# wavelet7.net
KiCad netlist of a schematic drawn in EAGLE
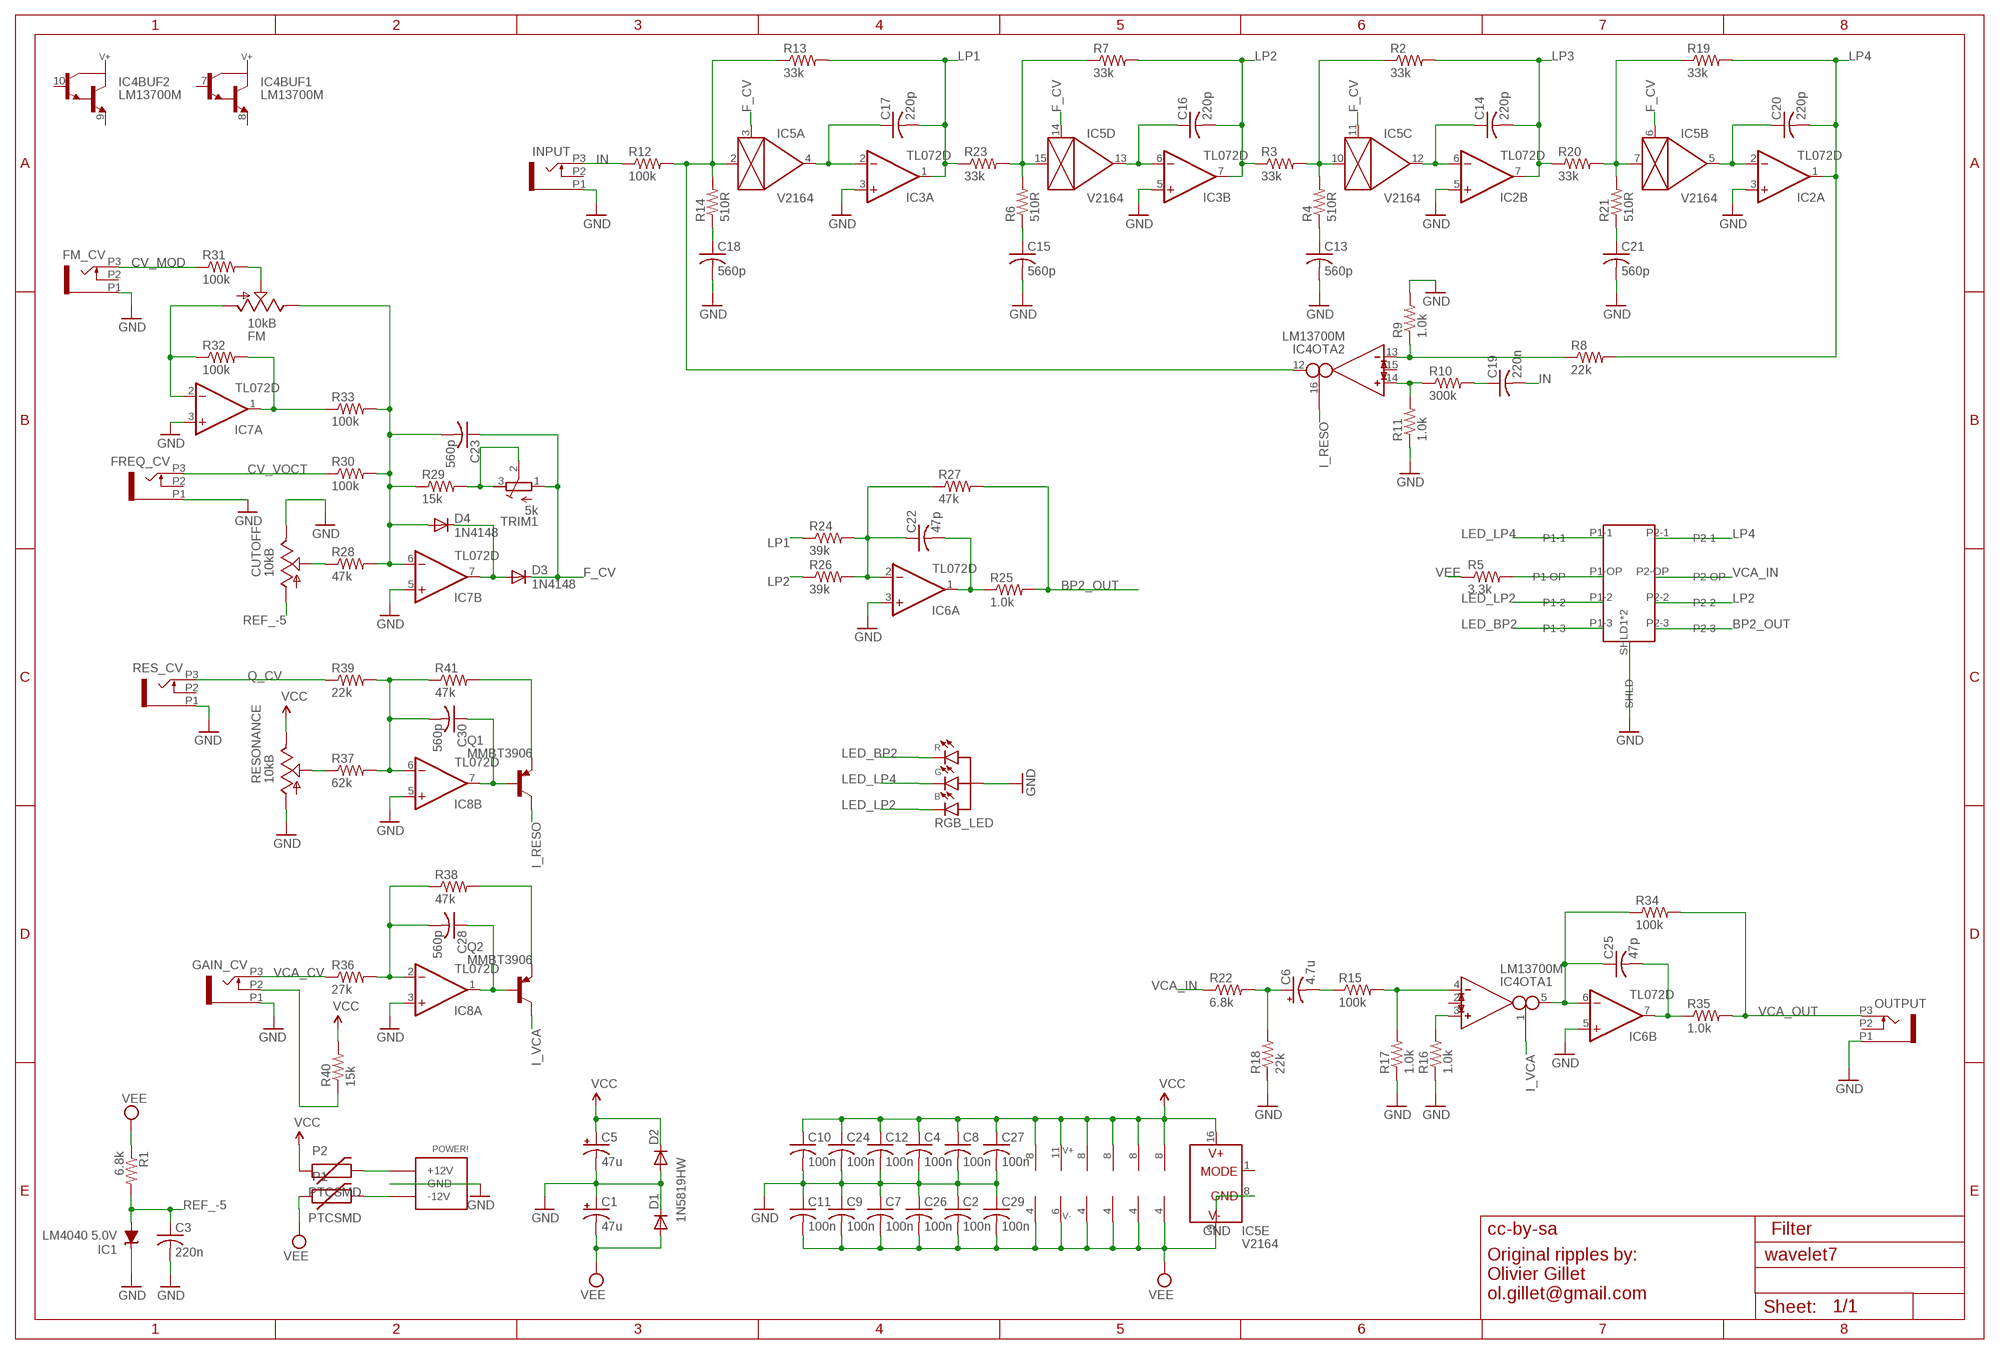
[diagram p0: schematic, sheet 1]

(export (version "E")
  (design (tool "Eeschema 10.0.6"))
  (components
    (comp (ref "C1")
      (value "47u")
      (footprint "eagle-import:PANASONIC_D")
      (libsource (lib "eagle-import") (part "CPOL-USD"))
    )
    (comp (ref "C2")
      (value "100n")
      (footprint "eagle-import:C0603")
      (libsource (lib "eagle-import") (part "C-USC0603"))
    )
    (comp (ref "C3")
      (value "220n")
      (footprint "eagle-import:C0603")
      (libsource (lib "eagle-import") (part "C-USC0603"))
    )
    (comp (ref "C4")
      (value "100n")
      (footprint "eagle-import:C0603")
      (libsource (lib "eagle-import") (part "C-USC0603"))
    )
    (comp (ref "C5")
      (value "47u")
      (footprint "eagle-import:PANASONIC_D")
      (libsource (lib "eagle-import") (part "CPOL-USD"))
    )
    (comp (ref "C6")
      (value "4.7u")
      (footprint "eagle-import:PANASONIC_B")
      (libsource (lib "eagle-import") (part "CPOL-USB"))
    )
    (comp (ref "C7")
      (value "100n")
      (footprint "eagle-import:C0603")
      (libsource (lib "eagle-import") (part "C-USC0603"))
    )
    (comp (ref "C8")
      (value "100n")
      (footprint "eagle-import:C0603")
      (libsource (lib "eagle-import") (part "C-USC0603"))
    )
    (comp (ref "C9")
      (value "100n")
      (footprint "eagle-import:C0603")
      (libsource (lib "eagle-import") (part "C-USC0603"))
    )
    (comp (ref "C10")
      (value "100n")
      (footprint "eagle-import:C0603")
      (libsource (lib "eagle-import") (part "C-USC0603"))
    )
    (comp (ref "C11")
      (value "100n")
      (footprint "eagle-import:C0603")
      (libsource (lib "eagle-import") (part "C-USC0603"))
    )
    (comp (ref "C12")
      (value "100n")
      (footprint "eagle-import:C0603")
      (libsource (lib "eagle-import") (part "C-USC0603"))
    )
    (comp (ref "C13")
      (value "560p")
      (footprint "eagle-import:C0603")
      (libsource (lib "eagle-import") (part "C-USC0603"))
    )
    (comp (ref "C14")
      (value "220p")
      (footprint "eagle-import:C0603")
      (libsource (lib "eagle-import") (part "C-USC0603"))
    )
    (comp (ref "C15")
      (value "560p")
      (footprint "eagle-import:C0603")
      (libsource (lib "eagle-import") (part "C-USC0603"))
    )
    (comp (ref "C16")
      (value "220p")
      (footprint "eagle-import:C0603")
      (libsource (lib "eagle-import") (part "C-USC0603"))
    )
    (comp (ref "C17")
      (value "220p")
      (footprint "eagle-import:C0603")
      (libsource (lib "eagle-import") (part "C-USC0603"))
    )
    (comp (ref "C18")
      (value "560p")
      (footprint "eagle-import:C0603")
      (libsource (lib "eagle-import") (part "C-USC0603"))
    )
    (comp (ref "C19")
      (value "220n")
      (footprint "eagle-import:C0603")
      (libsource (lib "eagle-import") (part "C-USC0603"))
    )
    (comp (ref "C20")
      (value "220p")
      (footprint "eagle-import:C0603")
      (libsource (lib "eagle-import") (part "C-USC0603"))
    )
    (comp (ref "C21")
      (value "560p")
      (footprint "eagle-import:C0603")
      (libsource (lib "eagle-import") (part "C-USC0603"))
    )
    (comp (ref "C22")
      (value "47p")
      (footprint "eagle-import:C0603")
      (libsource (lib "eagle-import") (part "C-USC0603"))
    )
    (comp (ref "C23")
      (value "560p")
      (footprint "eagle-import:C0603")
      (libsource (lib "eagle-import") (part "C-USC0603"))
    )
    (comp (ref "C24")
      (value "100n")
      (footprint "eagle-import:C0603")
      (libsource (lib "eagle-import") (part "C-USC0603"))
    )
    (comp (ref "C25")
      (value "47p")
      (footprint "eagle-import:C0603")
      (libsource (lib "eagle-import") (part "C-USC0603"))
    )
    (comp (ref "C26")
      (value "100n")
      (footprint "eagle-import:C0603")
      (libsource (lib "eagle-import") (part "C-USC0603"))
    )
    (comp (ref "C27")
      (value "100n")
      (footprint "eagle-import:C0603")
      (libsource (lib "eagle-import") (part "C-USC0603"))
    )
    (comp (ref "C28")
      (value "560p")
      (footprint "eagle-import:C0603")
      (libsource (lib "eagle-import") (part "C-USC0603"))
    )
    (comp (ref "C29")
      (value "100n")
      (footprint "eagle-import:C0603")
      (libsource (lib "eagle-import") (part "C-USC0603"))
    )
    (comp (ref "C30")
      (value "560p")
      (footprint "eagle-import:C0603")
      (libsource (lib "eagle-import") (part "C-USC0603"))
    )
    (comp (ref "CUTOFF")
      (value "10kB")
      (footprint "eagle-import:ALPS_POT_VERTICAL_PS")
      (libsource (lib "eagle-import") (part "POT_USVERTICAL_PS"))
    )
    (comp (ref "D1")
      (value "1N5819HW")
      (footprint "eagle-import:SOD123")
      (libsource (lib "eagle-import") (part "DIODE-SOD123"))
    )
    (comp (ref "D2")
      (value "1N5819HW")
      (footprint "eagle-import:SOD123")
      (libsource (lib "eagle-import") (part "DIODE-SOD123"))
    )
    (comp (ref "D3")
      (value "1N4148")
      (footprint "eagle-import:SOD323-W")
      (libsource (lib "eagle-import") (part "DIODE-SOD323-W"))
    )
    (comp (ref "D4")
      (value "1N4148")
      (footprint "eagle-import:SOD323-W")
      (libsource (lib "eagle-import") (part "DIODE-SOD323-W"))
    )
    (comp (ref "FILTER_MODE")
      (value "APEM-MHS233K")
      (footprint "eagle-import:APEM-MHS233K")
      (libsource (lib "eagle-import") (part "APEM-MHS233K"))
    )
    (comp (ref "FM")
      (value "10kB")
      (footprint "eagle-import:ALPS_POT_VERTICAL_PS")
      (libsource (lib "eagle-import") (part "POT_USVERTICAL_PS"))
    )
    (comp (ref "FM_CV")
      (value "OG-PJ301_PJ301_THONKICONN")
      (footprint "eagle-import:OG-PJ301_WQP_PJ_301M6_NO_HOLE")
      (libsource (lib "eagle-import") (part "OG-PJ301_PJ301_THONKICONN"))
    )
    (comp (ref "FREQ_CV")
      (value "OG-PJ301_PJ301_THONKICONN")
      (footprint "eagle-import:OG-PJ301_WQP_PJ_301M6_NO_HOLE")
      (libsource (lib "eagle-import") (part "OG-PJ301_PJ301_THONKICONN"))
    )
    (comp (ref "GAIN_CV")
      (value "OG-PJ301_PJ301_THONKICONN")
      (footprint "eagle-import:OG-PJ301_WQP_PJ_301M6_NO_HOLE")
      (libsource (lib "eagle-import") (part "OG-PJ301_PJ301_THONKICONN"))
    )
    (comp (ref "IC1")
      (value "LM4040 5.0V")
      (footprint "eagle-import:DBZ_R-PDSO-G3")
      (libsource (lib "eagle-import") (part "LM4041DBZC12"))
    )
    (comp (ref "IC2")
      (value "TL072D")
      (footprint "eagle-import:SO08")
      (libsource (lib "eagle-import") (part "og-linear_TL072D"))
    )
    (comp (ref "IC3")
      (value "TL072D")
      (footprint "eagle-import:SO08")
      (libsource (lib "eagle-import") (part "og-linear_TL072D"))
    )
    (comp (ref "IC4")
      (value "LM13700M")
      (footprint "eagle-import:SO16")
      (libsource (lib "eagle-import") (part "LM13700M"))
    )
    (comp (ref "IC5")
      (value "V2164")
      (footprint "eagle-import:SOIC16N")
      (libsource (lib "eagle-import") (part "SSM2164S"))
    )
    (comp (ref "IC6")
      (value "TL072D")
      (footprint "eagle-import:SO08")
      (libsource (lib "eagle-import") (part "TL072D"))
    )
    (comp (ref "IC7")
      (value "TL072D")
      (footprint "eagle-import:SO08")
      (libsource (lib "eagle-import") (part "TL072D"))
    )
    (comp (ref "IC8")
      (value "TL072D")
      (footprint "eagle-import:SO08")
      (libsource (lib "eagle-import") (part "TL072D"))
    )
    (comp (ref "INPUT")
      (value "OG-PJ301_PJ301_THONKICONN")
      (footprint "eagle-import:OG-PJ301_WQP_PJ_301M6_NO_HOLE")
      (libsource (lib "eagle-import") (part "OG-PJ301_PJ301_THONKICONN"))
    )
    (comp (ref "OUTPUT")
      (value "OG-PJ301_PJ301_THONKICONN")
      (footprint "eagle-import:OG-PJ301_WQP_PJ_301M6_NO_HOLE")
      (libsource (lib "eagle-import") (part "OG-PJ301_PJ301_THONKICONN"))
    )
    (comp (ref "P1")
      (value "PTCSMD")
      (footprint "eagle-import:PTC-1206")
      (libsource (lib "eagle-import") (part "PTCSMD"))
    )
    (comp (ref "P2")
      (value "PTCSMD")
      (footprint "eagle-import:PTC-1206")
      (libsource (lib "eagle-import") (part "PTCSMD"))
    )
    (comp (ref "POWER!")
      (value "POWER_SIMPLE")
      (footprint "eagle-import:2X05_SMT_HEADER")
      (libsource (lib "eagle-import") (part "POWER_SIMPLE"))
    )
    (comp (ref "Q1")
      (value "MMBT3906")
      (footprint "eagle-import:SOT23-BEC")
      (libsource (lib "eagle-import") (part "-PNP-SOT23-BECMMBT3906LT1"))
    )
    (comp (ref "Q2")
      (value "MMBT3906")
      (footprint "eagle-import:SOT23-BEC")
      (libsource (lib "eagle-import") (part "-PNP-SOT23-BECMMBT3906LT1"))
    )
    (comp (ref "R1")
      (value "6.8k")
      (footprint "eagle-import:R0603")
      (libsource (lib "eagle-import") (part "resistor_R-US_R0603"))
    )
    (comp (ref "R2")
      (value "33k")
      (footprint "eagle-import:R0603")
      (libsource (lib "eagle-import") (part "R-US_R0603"))
    )
    (comp (ref "R3")
      (value "33k")
      (footprint "eagle-import:R0603")
      (libsource (lib "eagle-import") (part "R-US_R0603"))
    )
    (comp (ref "R4")
      (value "510R")
      (footprint "eagle-import:R0603")
      (libsource (lib "eagle-import") (part "R-US_R0603"))
    )
    (comp (ref "R5")
      (value "3.3k")
      (footprint "eagle-import:R0603")
      (libsource (lib "eagle-import") (part "R-US_R0603"))
    )
    (comp (ref "R6")
      (value "510R")
      (footprint "eagle-import:R0603")
      (libsource (lib "eagle-import") (part "R-US_R0603"))
    )
    (comp (ref "R7")
      (value "33k")
      (footprint "eagle-import:R0603")
      (libsource (lib "eagle-import") (part "R-US_R0603"))
    )
    (comp (ref "R8")
      (value "22k")
      (footprint "eagle-import:R0603")
      (libsource (lib "eagle-import") (part "R-US_R0603"))
    )
    (comp (ref "R9")
      (value "1.0k")
      (footprint "eagle-import:R0603")
      (libsource (lib "eagle-import") (part "R-US_R0603"))
    )
    (comp (ref "R10")
      (value "300k")
      (footprint "eagle-import:R0603")
      (libsource (lib "eagle-import") (part "R-US_R0603"))
    )
    (comp (ref "R11")
      (value "1.0k")
      (footprint "eagle-import:R0603")
      (libsource (lib "eagle-import") (part "R-US_R0603"))
    )
    (comp (ref "R12")
      (value "100k")
      (footprint "eagle-import:R0603")
      (libsource (lib "eagle-import") (part "R-US_R0603"))
    )
    (comp (ref "R13")
      (value "33k")
      (footprint "eagle-import:R0603")
      (libsource (lib "eagle-import") (part "R-US_R0603"))
    )
    (comp (ref "R14")
      (value "510R")
      (footprint "eagle-import:R0603")
      (libsource (lib "eagle-import") (part "R-US_R0603"))
    )
    (comp (ref "R15")
      (value "100k")
      (footprint "eagle-import:R0603")
      (libsource (lib "eagle-import") (part "R-US_R0603"))
    )
    (comp (ref "R16")
      (value "1.0k")
      (footprint "eagle-import:R0603")
      (libsource (lib "eagle-import") (part "R-US_R0603"))
    )
    (comp (ref "R17")
      (value "1.0k")
      (footprint "eagle-import:R0603")
      (libsource (lib "eagle-import") (part "R-US_R0603"))
    )
    (comp (ref "R18")
      (value "22k")
      (footprint "eagle-import:R0603")
      (libsource (lib "eagle-import") (part "R-US_R0603"))
    )
    (comp (ref "R19")
      (value "33k")
      (footprint "eagle-import:R0603")
      (libsource (lib "eagle-import") (part "R-US_R0603"))
    )
    (comp (ref "R20")
      (value "33k")
      (footprint "eagle-import:R0603")
      (libsource (lib "eagle-import") (part "R-US_R0603"))
    )
    (comp (ref "R21")
      (value "510R")
      (footprint "eagle-import:R0603")
      (libsource (lib "eagle-import") (part "R-US_R0603"))
    )
    (comp (ref "R22")
      (value "6.8k")
      (footprint "eagle-import:R0603")
      (libsource (lib "eagle-import") (part "R-US_R0603"))
    )
    (comp (ref "R23")
      (value "33k")
      (footprint "eagle-import:R0603")
      (libsource (lib "eagle-import") (part "R-US_R0603"))
    )
    (comp (ref "R24")
      (value "39k")
      (footprint "eagle-import:R0603")
      (libsource (lib "eagle-import") (part "R-US_R0603"))
    )
    (comp (ref "R25")
      (value "1.0k")
      (footprint "eagle-import:R0603")
      (libsource (lib "eagle-import") (part "R-US_R0603"))
    )
    (comp (ref "R26")
      (value "39k")
      (footprint "eagle-import:R0603")
      (libsource (lib "eagle-import") (part "R-US_R0603"))
    )
    (comp (ref "R27")
      (value "47k")
      (footprint "eagle-import:R0603")
      (libsource (lib "eagle-import") (part "R-US_R0603"))
    )
    (comp (ref "R28")
      (value "47k")
      (footprint "eagle-import:R0603")
      (libsource (lib "eagle-import") (part "R-US_R0603"))
    )
    (comp (ref "R29")
      (value "15k")
      (footprint "eagle-import:R0603")
      (libsource (lib "eagle-import") (part "R-US_R0603"))
    )
    (comp (ref "R30")
      (value "100k")
      (footprint "eagle-import:R0603")
      (libsource (lib "eagle-import") (part "R-US_R0603"))
    )
    (comp (ref "R31")
      (value "100k")
      (footprint "eagle-import:R0603")
      (libsource (lib "eagle-import") (part "R-US_R0603"))
    )
    (comp (ref "R32")
      (value "100k")
      (footprint "eagle-import:R0603")
      (libsource (lib "eagle-import") (part "R-US_R0603"))
    )
    (comp (ref "R33")
      (value "100k")
      (footprint "eagle-import:R0603")
      (libsource (lib "eagle-import") (part "R-US_R0603"))
    )
    (comp (ref "R34")
      (value "100k")
      (footprint "eagle-import:R0603")
      (libsource (lib "eagle-import") (part "R-US_R0603"))
    )
    (comp (ref "R35")
      (value "1.0k")
      (footprint "eagle-import:R0603")
      (libsource (lib "eagle-import") (part "R-US_R0603"))
    )
    (comp (ref "R36")
      (value "27k")
      (footprint "eagle-import:R0603")
      (libsource (lib "eagle-import") (part "R-US_R0603"))
    )
    (comp (ref "R37")
      (value "62k")
      (footprint "eagle-import:R0603")
      (libsource (lib "eagle-import") (part "R-US_R0603"))
    )
    (comp (ref "R38")
      (value "47k")
      (footprint "eagle-import:R0603")
      (libsource (lib "eagle-import") (part "R-US_R0603"))
    )
    (comp (ref "R39")
      (value "22k")
      (footprint "eagle-import:R0603")
      (libsource (lib "eagle-import") (part "R-US_R0603"))
    )
    (comp (ref "R40")
      (value "15k")
      (footprint "eagle-import:R0603")
      (libsource (lib "eagle-import") (part "R-US_R0603"))
    )
    (comp (ref "R41")
      (value "47k")
      (footprint "eagle-import:R0603")
      (libsource (lib "eagle-import") (part "R-US_R0603"))
    )
    (comp (ref "RESONANCE")
      (value "10kB")
      (footprint "eagle-import:ALPS_POT_VERTICAL_PS")
      (libsource (lib "eagle-import") (part "POT_USVERTICAL_PS"))
    )
    (comp (ref "RES_CV")
      (value "OG-PJ301_PJ301_THONKICONN")
      (footprint "eagle-import:OG-PJ301_WQP_PJ_301M6_NO_HOLE")
      (libsource (lib "eagle-import") (part "OG-PJ301_PJ301_THONKICONN"))
    )
    (comp (ref "RGB_LED")
      (value "LED-RGB-CA-HEBEI")
      (footprint "eagle-import:PLCC4")
      (libsource (lib "eagle-import") (part "LED-RGB-CA-HEBEI"))
    )
    (comp (ref "TRIM1")
      (value "5k")
      (footprint "eagle-import:RTRIM3296X")
      (libsource (lib "eagle-import") (part "R-TRIMM3296X"))
    )
  )
  (nets
    (net (code "1") (name "/BP2_OUT") (class "Default")
      (node (ref "FILTER_MODE") (pin "P2-3") (pinfunction "P2-3_P2-3") (pintype "bidirectional"))
      (node (ref "R25") (pin "2") (pinfunction "2_2") (pintype "passive"))
      (node (ref "R27") (pin "2") (pinfunction "2_2") (pintype "passive"))
    )
    (net (code "2") (name "/CV_MOD") (class "Default")
      (node (ref "FM_CV") (pin "P3") (pinfunction "3_P3") (pintype "passive"))
      (node (ref "R31") (pin "1") (pinfunction "1_1") (pintype "passive"))
    )
    (net (code "3") (name "/CV_VOCT") (class "Default")
      (node (ref "FREQ_CV") (pin "P3") (pinfunction "3_P3") (pintype "passive"))
      (node (ref "R30") (pin "1") (pinfunction "1_1") (pintype "passive"))
    )
    (net (code "4") (name "/F_CV") (class "Default")
      (node (ref "C23") (pin "1") (pinfunction "1_1") (pintype "passive"))
      (node (ref "D3") (pin "C") (pinfunction "C_C") (pintype "passive"))
      (node (ref "IC5") (pin "11") (pinfunction "CTRL_11") (pintype "input"))
      (node (ref "IC5") (pin "14") (pinfunction "CTRL_14") (pintype "input"))
      (node (ref "IC5") (pin "3") (pinfunction "CTRL_3") (pintype "input"))
      (node (ref "IC5") (pin "6") (pinfunction "CTRL_6") (pintype "input"))
      (node (ref "TRIM1") (pin "1") (pinfunction "E_1") (pintype "passive"))
    )
    (net (code "5") (name "/IN") (class "Default")
      (node (ref "C19") (pin "2") (pinfunction "2_2") (pintype "passive"))
      (node (ref "INPUT") (pin "P3") (pinfunction "3_P3") (pintype "passive"))
      (node (ref "R12") (pin "1") (pinfunction "1_1") (pintype "passive"))
    )
    (net (code "6") (name "/I_RESO") (class "Default")
      (node (ref "IC4") (pin "16") (pinfunction "I_BIAS_16") (pintype "input"))
      (node (ref "Q1") (pin "C") (pinfunction "C_C") (pintype "passive"))
    )
    (net (code "7") (name "/I_VCA") (class "Default")
      (node (ref "IC4") (pin "1") (pinfunction "I_BIAS_1") (pintype "input"))
      (node (ref "Q2") (pin "C") (pinfunction "C_C") (pintype "passive"))
    )
    (net (code "8") (name "/LED_BP2") (class "Default")
      (node (ref "FILTER_MODE") (pin "P1-3") (pinfunction "P1-3_P1-3") (pintype "bidirectional"))
      (node (ref "RGB_LED") (pin "P$1") (pinfunction "CR_P$1") (pintype "passive"))
    )
    (net (code "9") (name "/LED_LP2") (class "Default")
      (node (ref "FILTER_MODE") (pin "P1-2") (pinfunction "P1-2_P1-2") (pintype "bidirectional"))
      (node (ref "RGB_LED") (pin "P$3") (pinfunction "CB_P$3") (pintype "passive"))
    )
    (net (code "10") (name "/LED_LP4") (class "Default")
      (node (ref "FILTER_MODE") (pin "P1-1") (pinfunction "P1-1_P1-1") (pintype "bidirectional"))
      (node (ref "RGB_LED") (pin "P$4") (pinfunction "CG_P$4") (pintype "passive"))
    )
    (net (code "11") (name "/LP1") (class "Default")
      (node (ref "C17") (pin "2") (pinfunction "2_2") (pintype "passive"))
      (node (ref "IC3") (pin "1") (pinfunction "OUT_1") (pintype "output"))
      (node (ref "R13") (pin "2") (pinfunction "2_2") (pintype "passive"))
      (node (ref "R23") (pin "1") (pinfunction "1_1") (pintype "passive"))
      (node (ref "R24") (pin "1") (pinfunction "1_1") (pintype "passive"))
    )
    (net (code "12") (name "/LP2") (class "Default")
      (node (ref "C16") (pin "2") (pinfunction "2_2") (pintype "passive"))
      (node (ref "FILTER_MODE") (pin "P2-2") (pinfunction "P2-2_P2-2") (pintype "bidirectional"))
      (node (ref "IC3") (pin "7") (pinfunction "OUT_7") (pintype "output"))
      (node (ref "R26") (pin "1") (pinfunction "1_1") (pintype "passive"))
      (node (ref "R3") (pin "1") (pinfunction "1_1") (pintype "passive"))
      (node (ref "R7") (pin "2") (pinfunction "2_2") (pintype "passive"))
    )
    (net (code "13") (name "/LP3") (class "Default")
      (node (ref "C14") (pin "2") (pinfunction "2_2") (pintype "passive"))
      (node (ref "IC2") (pin "7") (pinfunction "OUT_7") (pintype "output"))
      (node (ref "R2") (pin "2") (pinfunction "2_2") (pintype "passive"))
      (node (ref "R20") (pin "1") (pinfunction "1_1") (pintype "passive"))
    )
    (net (code "14") (name "/LP4") (class "Default")
      (node (ref "C20") (pin "2") (pinfunction "2_2") (pintype "passive"))
      (node (ref "FILTER_MODE") (pin "P2-1") (pinfunction "P2-1_P2-1") (pintype "bidirectional"))
      (node (ref "IC2") (pin "1") (pinfunction "OUT_1") (pintype "output"))
      (node (ref "R19") (pin "2") (pinfunction "2_2") (pintype "passive"))
      (node (ref "R8") (pin "2") (pinfunction "2_2") (pintype "passive"))
    )
    (net (code "15") (name "/Q_CV") (class "Default")
      (node (ref "R39") (pin "1") (pinfunction "1_1") (pintype "passive"))
      (node (ref "RES_CV") (pin "P3") (pinfunction "3_P3") (pintype "passive"))
    )
    (net (code "16") (name "/REF_-5") (class "Default")
      (node (ref "C3") (pin "1") (pinfunction "1_1") (pintype "passive"))
      (node (ref "CUTOFF") (pin "P$3") (pinfunction "A_P$3") (pintype "passive"))
      (node (ref "IC1") (pin "2") (pinfunction "A_2") (pintype "passive"))
      (node (ref "R1") (pin "2") (pinfunction "2_2") (pintype "passive"))
    )
    (net (code "17") (name "/VCA_CV") (class "Default")
      (node (ref "GAIN_CV") (pin "P3") (pinfunction "3_P3") (pintype "passive"))
      (node (ref "R36") (pin "1") (pinfunction "1_1") (pintype "passive"))
    )
    (net (code "18") (name "/VCA_IN") (class "Default")
      (node (ref "FILTER_MODE") (pin "P2-OP") (pinfunction "P2-OP_P2-OP") (pintype "bidirectional"))
      (node (ref "R22") (pin "1") (pinfunction "1_1") (pintype "passive"))
    )
    (net (code "19") (name "/VCA_OUT") (class "Default")
      (node (ref "OUTPUT") (pin "P3") (pinfunction "3_P3") (pintype "passive"))
      (node (ref "R34") (pin "2") (pinfunction "2_2") (pintype "passive"))
      (node (ref "R35") (pin "2") (pinfunction "2_2") (pintype "passive"))
    )
    (net (code "20") (name "GND") (class "Default")
      (node (ref "C1") (pin "+") (pinfunction "+_+") (pintype "passive"))
      (node (ref "C10") (pin "2") (pinfunction "2_2") (pintype "passive"))
      (node (ref "C11") (pin "1") (pinfunction "1_1") (pintype "passive"))
      (node (ref "C12") (pin "2") (pinfunction "2_2") (pintype "passive"))
      (node (ref "C13") (pin "2") (pinfunction "2_2") (pintype "passive"))
      (node (ref "C15") (pin "2") (pinfunction "2_2") (pintype "passive"))
      (node (ref "C18") (pin "2") (pinfunction "2_2") (pintype "passive"))
      (node (ref "C2") (pin "1") (pinfunction "1_1") (pintype "passive"))
      (node (ref "C21") (pin "2") (pinfunction "2_2") (pintype "passive"))
      (node (ref "C24") (pin "2") (pinfunction "2_2") (pintype "passive"))
      (node (ref "C26") (pin "1") (pinfunction "1_1") (pintype "passive"))
      (node (ref "C27") (pin "2") (pinfunction "2_2") (pintype "passive"))
      (node (ref "C29") (pin "1") (pinfunction "1_1") (pintype "passive"))
      (node (ref "C3") (pin "2") (pinfunction "2_2") (pintype "passive"))
      (node (ref "C4") (pin "2") (pinfunction "2_2") (pintype "passive"))
      (node (ref "C5") (pin "-") (pinfunction "-_-") (pintype "passive"))
      (node (ref "C7") (pin "1") (pinfunction "1_1") (pintype "passive"))
      (node (ref "C8") (pin "2") (pinfunction "2_2") (pintype "passive"))
      (node (ref "C9") (pin "1") (pinfunction "1_1") (pintype "passive"))
      (node (ref "CUTOFF") (pin "P$1") (pinfunction "E_P$1") (pintype "passive"))
      (node (ref "D1") (pin "C") (pinfunction "C_C") (pintype "passive"))
      (node (ref "D2") (pin "A") (pinfunction "A_A") (pintype "passive"))
      (node (ref "FILTER_MODE") (pin "SHLD1") (pinfunction "SHLD_SHLD1") (pintype "bidirectional"))
      (node (ref "FILTER_MODE") (pin "SHLD2") (pinfunction "SHLD_SHLD2") (pintype "bidirectional"))
      (node (ref "FM_CV") (pin "P1") (pinfunction "1_P1") (pintype "passive"))
      (node (ref "FREQ_CV") (pin "P1") (pinfunction "1_P1") (pintype "passive"))
      (node (ref "GAIN_CV") (pin "P1") (pinfunction "1_P1") (pintype "passive"))
      (node (ref "IC1") (pin "1") (pinfunction "C_1") (pintype "passive"))
      (node (ref "IC2") (pin "3") (pinfunction "+IN_3") (pintype "input"))
      (node (ref "IC2") (pin "5") (pinfunction "+IN_5") (pintype "input"))
      (node (ref "IC3") (pin "3") (pinfunction "+IN_3") (pintype "input"))
      (node (ref "IC3") (pin "5") (pinfunction "+IN_5") (pintype "input"))
      (node (ref "IC5") (pin "8") (pinfunction "GND_8") (pintype "power_in"))
      (node (ref "IC6") (pin "3") (pinfunction "+IN_3") (pintype "input"))
      (node (ref "IC6") (pin "5") (pinfunction "+IN_5") (pintype "input"))
      (node (ref "IC7") (pin "3") (pinfunction "+IN_3") (pintype "input"))
      (node (ref "IC7") (pin "5") (pinfunction "+IN_5") (pintype "input"))
      (node (ref "IC8") (pin "3") (pinfunction "+IN_3") (pintype "input"))
      (node (ref "IC8") (pin "5") (pinfunction "+IN_5") (pintype "input"))
      (node (ref "INPUT") (pin "P1") (pinfunction "1_P1") (pintype "passive"))
      (node (ref "OUTPUT") (pin "P1") (pinfunction "1_P1") (pintype "passive"))
      (node (ref "POWER!") (pin "3") (pinfunction "GND_3") (pintype "bidirectional"))
      (node (ref "POWER!") (pin "4") (pinfunction "GND_4") (pintype "bidirectional"))
      (node (ref "POWER!") (pin "5") (pinfunction "GND_5") (pintype "bidirectional"))
      (node (ref "POWER!") (pin "6") (pinfunction "GND_6") (pintype "bidirectional"))
      (node (ref "POWER!") (pin "7") (pinfunction "GND_7") (pintype "bidirectional"))
      (node (ref "POWER!") (pin "8") (pinfunction "GND_8") (pintype "bidirectional"))
      (node (ref "R11") (pin "1") (pinfunction "1_1") (pintype "passive"))
      (node (ref "R16") (pin "1") (pinfunction "1_1") (pintype "passive"))
      (node (ref "R17") (pin "1") (pinfunction "1_1") (pintype "passive"))
      (node (ref "R18") (pin "1") (pinfunction "1_1") (pintype "passive"))
      (node (ref "R9") (pin "2") (pinfunction "2_2") (pintype "passive"))
      (node (ref "RESONANCE") (pin "P$3") (pinfunction "A_P$3") (pintype "passive"))
      (node (ref "RES_CV") (pin "P1") (pinfunction "1_P1") (pintype "passive"))
      (node (ref "RGB_LED") (pin "P$2") (pinfunction "A_P$2") (pintype "passive"))
    )
    (net (code "21") (name "Net-(C6-Pad+)") (class "Default")
      (node (ref "C6") (pin "+") (pinfunction "+_+") (pintype "passive"))
      (node (ref "R18") (pin "2") (pinfunction "2_2") (pintype "passive"))
      (node (ref "R22") (pin "2") (pinfunction "2_2") (pintype "passive"))
    )
    (net (code "22") (name "Net-(C6-Pad-)") (class "Default")
      (node (ref "C6") (pin "-") (pinfunction "-_-") (pintype "passive"))
      (node (ref "R15") (pin "1") (pinfunction "1_1") (pintype "passive"))
    )
    (net (code "23") (name "Net-(C13-Pad1)") (class "Default")
      (node (ref "C13") (pin "1") (pinfunction "1_1") (pintype "passive"))
      (node (ref "R4") (pin "1") (pinfunction "1_1") (pintype "passive"))
    )
    (net (code "24") (name "Net-(C15-Pad1)") (class "Default")
      (node (ref "C15") (pin "1") (pinfunction "1_1") (pintype "passive"))
      (node (ref "R6") (pin "1") (pinfunction "1_1") (pintype "passive"))
    )
    (net (code "25") (name "Net-(C18-Pad1)") (class "Default")
      (node (ref "C18") (pin "1") (pinfunction "1_1") (pintype "passive"))
      (node (ref "R14") (pin "1") (pinfunction "1_1") (pintype "passive"))
    )
    (net (code "26") (name "Net-(C19-Pad1)") (class "Default")
      (node (ref "C19") (pin "1") (pinfunction "1_1") (pintype "passive"))
      (node (ref "R10") (pin "2") (pinfunction "2_2") (pintype "passive"))
    )
    (net (code "27") (name "Net-(C21-Pad1)") (class "Default")
      (node (ref "C21") (pin "1") (pinfunction "1_1") (pintype "passive"))
      (node (ref "R21") (pin "1") (pinfunction "1_1") (pintype "passive"))
    )
    (net (code "28") (name "Net-(CUTOFF-S)") (class "Default")
      (node (ref "CUTOFF") (pin "P$2") (pinfunction "S_P$2") (pintype "passive"))
      (node (ref "R28") (pin "1") (pinfunction "1_1") (pintype "passive"))
    )
    (net (code "29") (name "Net-(FILTER_MODE-PadP1-OP)") (class "Default")
      (node (ref "FILTER_MODE") (pin "P1-OP") (pinfunction "P1-OP_P1-OP") (pintype "bidirectional"))
      (node (ref "R5") (pin "2") (pinfunction "2_2") (pintype "passive"))
    )
    (net (code "30") (name "Net-(FM-A)") (class "Default")
      (node (ref "FM") (pin "P$3") (pinfunction "A_P$3") (pintype "passive"))
      (node (ref "IC7") (pin "2") (pinfunction "-IN_2") (pintype "input"))
      (node (ref "R32") (pin "1") (pinfunction "1_1") (pintype "passive"))
    )
    (net (code "31") (name "Net-(FM-E)") (class "Default")
      (node (ref "C23") (pin "2") (pinfunction "2_2") (pintype "passive"))
      (node (ref "D4") (pin "A") (pinfunction "A_A") (pintype "passive"))
      (node (ref "FM") (pin "P$1") (pinfunction "E_P$1") (pintype "passive"))
      (node (ref "IC7") (pin "6") (pinfunction "-IN_6") (pintype "input"))
      (node (ref "R28") (pin "2") (pinfunction "2_2") (pintype "passive"))
      (node (ref "R29") (pin "1") (pinfunction "1_1") (pintype "passive"))
      (node (ref "R30") (pin "2") (pinfunction "2_2") (pintype "passive"))
      (node (ref "R33") (pin "2") (pinfunction "2_2") (pintype "passive"))
    )
    (net (code "32") (name "Net-(FM-S)") (class "Default")
      (node (ref "FM") (pin "P$2") (pinfunction "S_P$2") (pintype "passive"))
      (node (ref "R31") (pin "2") (pinfunction "2_2") (pintype "passive"))
    )
    (net (code "33") (name "Net-(GAIN_CV-2)") (class "Default")
      (node (ref "GAIN_CV") (pin "P2") (pinfunction "2_P2") (pintype "passive"))
      (node (ref "R40") (pin "1") (pinfunction "1_1") (pintype "passive"))
    )
    (net (code "34") (name "Net-(IC2A--IN)") (class "Default")
      (node (ref "C20") (pin "1") (pinfunction "1_1") (pintype "passive"))
      (node (ref "IC2") (pin "2") (pinfunction "-IN_2") (pintype "input"))
      (node (ref "IC5") (pin "5") (pinfunction "OUT_5") (pintype "output"))
    )
    (net (code "35") (name "Net-(IC2B--IN)") (class "Default")
      (node (ref "C14") (pin "1") (pinfunction "1_1") (pintype "passive"))
      (node (ref "IC2") (pin "6") (pinfunction "-IN_6") (pintype "input"))
      (node (ref "IC5") (pin "12") (pinfunction "OUT_12") (pintype "output"))
    )
    (net (code "36") (name "Net-(IC3A--IN)") (class "Default")
      (node (ref "C17") (pin "1") (pinfunction "1_1") (pintype "passive"))
      (node (ref "IC3") (pin "2") (pinfunction "-IN_2") (pintype "input"))
      (node (ref "IC5") (pin "4") (pinfunction "OUT_4") (pintype "output"))
    )
    (net (code "37") (name "Net-(IC3B--IN)") (class "Default")
      (node (ref "C16") (pin "1") (pinfunction "1_1") (pintype "passive"))
      (node (ref "IC3") (pin "6") (pinfunction "-IN_6") (pintype "input"))
      (node (ref "IC5") (pin "13") (pinfunction "OUT_13") (pintype "output"))
    )
    (net (code "38") (name "Net-(IC4C-IN_N)") (class "Default")
      (node (ref "IC4") (pin "4") (pinfunction "IN_N_4") (pintype "input"))
      (node (ref "R15") (pin "2") (pinfunction "2_2") (pintype "passive"))
      (node (ref "R17") (pin "2") (pinfunction "2_2") (pintype "passive"))
    )
    (net (code "39") (name "Net-(IC4C-IN_P)") (class "Default")
      (node (ref "IC4") (pin "3") (pinfunction "IN_P_3") (pintype "input"))
      (node (ref "R16") (pin "2") (pinfunction "2_2") (pintype "passive"))
    )
    (net (code "40") (name "Net-(IC4C-OUT)") (class "Default")
      (node (ref "C25") (pin "1") (pinfunction "1_1") (pintype "passive"))
      (node (ref "IC4") (pin "5") (pinfunction "OUT_5") (pintype "output"))
      (node (ref "IC6") (pin "6") (pinfunction "-IN_6") (pintype "input"))
      (node (ref "R34") (pin "1") (pinfunction "1_1") (pintype "passive"))
    )
    (net (code "41") (name "Net-(IC4D-IN_N)") (class "Default")
      (node (ref "IC4") (pin "13") (pinfunction "IN_N_13") (pintype "input"))
      (node (ref "R8") (pin "1") (pinfunction "1_1") (pintype "passive"))
      (node (ref "R9") (pin "1") (pinfunction "1_1") (pintype "passive"))
    )
    (net (code "42") (name "Net-(IC4D-IN_P)") (class "Default")
      (node (ref "IC4") (pin "14") (pinfunction "IN_P_14") (pintype "input"))
      (node (ref "R10") (pin "1") (pinfunction "1_1") (pintype "passive"))
      (node (ref "R11") (pin "2") (pinfunction "2_2") (pintype "passive"))
    )
    (net (code "43") (name "Net-(IC4D-OUT)") (class "Default")
      (node (ref "IC4") (pin "12") (pinfunction "OUT_12") (pintype "output"))
      (node (ref "IC5") (pin "2") (pinfunction "IN_2") (pintype "input"))
      (node (ref "R12") (pin "2") (pinfunction "2_2") (pintype "passive"))
      (node (ref "R13") (pin "1") (pinfunction "1_1") (pintype "passive"))
      (node (ref "R14") (pin "2") (pinfunction "2_2") (pintype "passive"))
    )
    (net (code "44") (name "Net-(IC5B-IN)") (class "Default")
      (node (ref "IC5") (pin "7") (pinfunction "IN_7") (pintype "input"))
      (node (ref "R19") (pin "1") (pinfunction "1_1") (pintype "passive"))
      (node (ref "R20") (pin "2") (pinfunction "2_2") (pintype "passive"))
      (node (ref "R21") (pin "2") (pinfunction "2_2") (pintype "passive"))
    )
    (net (code "45") (name "Net-(IC5C-IN)") (class "Default")
      (node (ref "IC5") (pin "10") (pinfunction "IN_10") (pintype "input"))
      (node (ref "R2") (pin "1") (pinfunction "1_1") (pintype "passive"))
      (node (ref "R3") (pin "2") (pinfunction "2_2") (pintype "passive"))
      (node (ref "R4") (pin "2") (pinfunction "2_2") (pintype "passive"))
    )
    (net (code "46") (name "Net-(IC5D-IN)") (class "Default")
      (node (ref "IC5") (pin "15") (pinfunction "IN_15") (pintype "input"))
      (node (ref "R23") (pin "2") (pinfunction "2_2") (pintype "passive"))
      (node (ref "R6") (pin "2") (pinfunction "2_2") (pintype "passive"))
      (node (ref "R7") (pin "1") (pinfunction "1_1") (pintype "passive"))
    )
    (net (code "47") (name "Net-(IC6A--IN)") (class "Default")
      (node (ref "C22") (pin "1") (pinfunction "1_1") (pintype "passive"))
      (node (ref "IC6") (pin "2") (pinfunction "-IN_2") (pintype "input"))
      (node (ref "R24") (pin "2") (pinfunction "2_2") (pintype "passive"))
      (node (ref "R26") (pin "2") (pinfunction "2_2") (pintype "passive"))
      (node (ref "R27") (pin "1") (pinfunction "1_1") (pintype "passive"))
    )
    (net (code "48") (name "Net-(IC6A-OUT)") (class "Default")
      (node (ref "C22") (pin "2") (pinfunction "2_2") (pintype "passive"))
      (node (ref "IC6") (pin "1") (pinfunction "OUT_1") (pintype "output"))
      (node (ref "R25") (pin "1") (pinfunction "1_1") (pintype "passive"))
    )
    (net (code "49") (name "Net-(IC6B-OUT)") (class "Default")
      (node (ref "C25") (pin "2") (pinfunction "2_2") (pintype "passive"))
      (node (ref "IC6") (pin "7") (pinfunction "OUT_7") (pintype "output"))
      (node (ref "R35") (pin "1") (pinfunction "1_1") (pintype "passive"))
    )
    (net (code "50") (name "Net-(IC7A-OUT)") (class "Default")
      (node (ref "IC7") (pin "1") (pinfunction "OUT_1") (pintype "output"))
      (node (ref "R32") (pin "2") (pinfunction "2_2") (pintype "passive"))
      (node (ref "R33") (pin "1") (pinfunction "1_1") (pintype "passive"))
    )
    (net (code "51") (name "Net-(IC7B-OUT)") (class "Default")
      (node (ref "D3") (pin "A") (pinfunction "A_A") (pintype "passive"))
      (node (ref "D4") (pin "C") (pinfunction "C_C") (pintype "passive"))
      (node (ref "IC7") (pin "7") (pinfunction "OUT_7") (pintype "output"))
    )
    (net (code "52") (name "Net-(IC8A--IN)") (class "Default")
      (node (ref "C28") (pin "2") (pinfunction "2_2") (pintype "passive"))
      (node (ref "IC8") (pin "2") (pinfunction "-IN_2") (pintype "input"))
      (node (ref "R36") (pin "2") (pinfunction "2_2") (pintype "passive"))
      (node (ref "R38") (pin "1") (pinfunction "1_1") (pintype "passive"))
    )
    (net (code "53") (name "Net-(IC8A-OUT)") (class "Default")
      (node (ref "C28") (pin "1") (pinfunction "1_1") (pintype "passive"))
      (node (ref "IC8") (pin "1") (pinfunction "OUT_1") (pintype "output"))
      (node (ref "Q2") (pin "B") (pinfunction "B_B") (pintype "passive"))
    )
    (net (code "54") (name "Net-(IC8B--IN)") (class "Default")
      (node (ref "C30") (pin "2") (pinfunction "2_2") (pintype "passive"))
      (node (ref "IC8") (pin "6") (pinfunction "-IN_6") (pintype "input"))
      (node (ref "R37") (pin "2") (pinfunction "2_2") (pintype "passive"))
      (node (ref "R39") (pin "2") (pinfunction "2_2") (pintype "passive"))
      (node (ref "R41") (pin "1") (pinfunction "1_1") (pintype "passive"))
    )
    (net (code "55") (name "Net-(IC8B-OUT)") (class "Default")
      (node (ref "C30") (pin "1") (pinfunction "1_1") (pintype "passive"))
      (node (ref "IC8") (pin "7") (pinfunction "OUT_7") (pintype "output"))
      (node (ref "Q1") (pin "B") (pinfunction "B_B") (pintype "passive"))
    )
    (net (code "56") (name "Net-(P1-Pad2)") (class "Default")
      (node (ref "P1") (pin "2") (pinfunction "2_2") (pintype "bidirectional"))
      (node (ref "POWER!") (pin "1") (pinfunction "-12V_1") (pintype "bidirectional"))
      (node (ref "POWER!") (pin "2") (pinfunction "-12V_2") (pintype "bidirectional"))
    )
    (net (code "57") (name "Net-(P2-Pad2)") (class "Default")
      (node (ref "P2") (pin "2") (pinfunction "2_2") (pintype "bidirectional"))
      (node (ref "POWER!") (pin "10") (pinfunction "+12V_10") (pintype "bidirectional"))
      (node (ref "POWER!") (pin "9") (pinfunction "+12V_9") (pintype "bidirectional"))
    )
    (net (code "58") (name "Net-(Q1-PadE)") (class "Default")
      (node (ref "Q1") (pin "E") (pinfunction "E_E") (pintype "passive"))
      (node (ref "R41") (pin "2") (pinfunction "2_2") (pintype "passive"))
    )
    (net (code "59") (name "Net-(Q2-PadE)") (class "Default")
      (node (ref "Q2") (pin "E") (pinfunction "E_E") (pintype "passive"))
      (node (ref "R38") (pin "2") (pinfunction "2_2") (pintype "passive"))
    )
    (net (code "60") (name "Net-(RESONANCE-S)") (class "Default")
      (node (ref "R37") (pin "1") (pinfunction "1_1") (pintype "passive"))
      (node (ref "RESONANCE") (pin "P$2") (pinfunction "S_P$2") (pintype "passive"))
    )
    (net (code "61") (name "Net-(TRIM1-A)") (class "Default")
      (node (ref "R29") (pin "2") (pinfunction "2_2") (pintype "passive"))
      (node (ref "TRIM1") (pin "2") (pinfunction "S_2") (pintype "passive"))
      (node (ref "TRIM1") (pin "3") (pinfunction "A_3") (pintype "passive"))
    )
    (net (code "62") (name "VCC") (class "Default")
      (node (ref "C10") (pin "1") (pinfunction "1_1") (pintype "passive"))
      (node (ref "C12") (pin "1") (pinfunction "1_1") (pintype "passive"))
      (node (ref "C24") (pin "1") (pinfunction "1_1") (pintype "passive"))
      (node (ref "C27") (pin "1") (pinfunction "1_1") (pintype "passive"))
      (node (ref "C4") (pin "1") (pinfunction "1_1") (pintype "passive"))
      (node (ref "C5") (pin "+") (pinfunction "+_+") (pintype "passive"))
      (node (ref "C8") (pin "1") (pinfunction "1_1") (pintype "passive"))
      (node (ref "D2") (pin "C") (pinfunction "C_C") (pintype "passive"))
      (node (ref "IC2") (pin "8") (pinfunction "V+_8") (pintype "power_in"))
      (node (ref "IC3") (pin "8") (pinfunction "V+_8") (pintype "power_in"))
      (node (ref "IC4") (pin "11") (pinfunction "V+_11") (pintype "power_in"))
      (node (ref "IC5") (pin "16") (pinfunction "V+_16") (pintype "power_in"))
      (node (ref "IC6") (pin "8") (pinfunction "V+_8") (pintype "power_in"))
      (node (ref "IC7") (pin "8") (pinfunction "V+_8") (pintype "power_in"))
      (node (ref "IC8") (pin "8") (pinfunction "V+_8") (pintype "power_in"))
      (node (ref "P2") (pin "1") (pinfunction "1_1") (pintype "bidirectional"))
      (node (ref "R40") (pin "2") (pinfunction "2_2") (pintype "passive"))
      (node (ref "RESONANCE") (pin "P$1") (pinfunction "E_P$1") (pintype "passive"))
    )
    (net (code "63") (name "VEE") (class "Default")
      (node (ref "C1") (pin "-") (pinfunction "-_-") (pintype "passive"))
      (node (ref "C11") (pin "2") (pinfunction "2_2") (pintype "passive"))
      (node (ref "C2") (pin "2") (pinfunction "2_2") (pintype "passive"))
      (node (ref "C26") (pin "2") (pinfunction "2_2") (pintype "passive"))
      (node (ref "C29") (pin "2") (pinfunction "2_2") (pintype "passive"))
      (node (ref "C7") (pin "2") (pinfunction "2_2") (pintype "passive"))
      (node (ref "C9") (pin "2") (pinfunction "2_2") (pintype "passive"))
      (node (ref "D1") (pin "A") (pinfunction "A_A") (pintype "passive"))
      (node (ref "IC2") (pin "4") (pinfunction "V-_4") (pintype "power_in"))
      (node (ref "IC3") (pin "4") (pinfunction "V-_4") (pintype "power_in"))
      (node (ref "IC4") (pin "6") (pinfunction "V-_6") (pintype "power_in"))
      (node (ref "IC5") (pin "9") (pinfunction "V-_9") (pintype "power_in"))
      (node (ref "IC6") (pin "4") (pinfunction "V-_4") (pintype "power_in"))
      (node (ref "IC7") (pin "4") (pinfunction "V-_4") (pintype "power_in"))
      (node (ref "IC8") (pin "4") (pinfunction "V-_4") (pintype "power_in"))
      (node (ref "P1") (pin "1") (pinfunction "1_1") (pintype "bidirectional"))
      (node (ref "R1") (pin "1") (pinfunction "1_1") (pintype "passive"))
      (node (ref "R5") (pin "1") (pinfunction "1_1") (pintype "passive"))
    )
    (net (code "64") (name "unconnected-(FM_CV-2-PadP2)") (class "Default")
      (node (ref "FM_CV") (pin "P2") (pinfunction "2_P2") (pintype "passive"))
    )
    (net (code "65") (name "unconnected-(FREQ_CV-2-PadP2)") (class "Default")
      (node (ref "FREQ_CV") (pin "P2") (pinfunction "2_P2") (pintype "passive"))
    )
    (net (code "66") (name "unconnected-(IC4A-B-Pad7)") (class "Default")
      (node (ref "IC4") (pin "7") (pinfunction "B_7") (pintype "passive"))
    )
    (net (code "67") (name "unconnected-(IC4A-E-Pad8)") (class "Default")
      (node (ref "IC4") (pin "8") (pinfunction "E_8") (pintype "passive"))
    )
    (net (code "68") (name "unconnected-(IC4B-B-Pad10)") (class "Default")
      (node (ref "IC4") (pin "10") (pinfunction "B_10") (pintype "passive"))
    )
    (net (code "69") (name "unconnected-(IC4B-E-Pad9)") (class "Default")
      (node (ref "IC4") (pin "9") (pinfunction "E_9") (pintype "passive"))
    )
    (net (code "70") (name "unconnected-(IC4C-I_DIODE-Pad2)") (class "Default")
      (node (ref "IC4") (pin "2") (pinfunction "I_DIODE_2") (pintype "input"))
    )
    (net (code "71") (name "unconnected-(IC4D-I_DIODE-Pad15)") (class "Default")
      (node (ref "IC4") (pin "15") (pinfunction "I_DIODE_15") (pintype "input"))
    )
    (net (code "72") (name "unconnected-(IC5E-MODE-Pad1)") (class "Default")
      (node (ref "IC5") (pin "1") (pinfunction "MODE_1") (pintype "input"))
    )
    (net (code "73") (name "unconnected-(INPUT-2-PadP2)") (class "Default")
      (node (ref "INPUT") (pin "P2") (pinfunction "2_P2") (pintype "passive"))
    )
    (net (code "74") (name "unconnected-(OUTPUT-2-PadP2)") (class "Default")
      (node (ref "OUTPUT") (pin "P2") (pinfunction "2_P2") (pintype "passive"))
    )
    (net (code "75") (name "unconnected-(RES_CV-2-PadP2)") (class "Default")
      (node (ref "RES_CV") (pin "P2") (pinfunction "2_P2") (pintype "passive"))
    )
  )
)
